# TPS54622_Schematic.net
KiCad netlist of a schematic drawn in Altium Designer
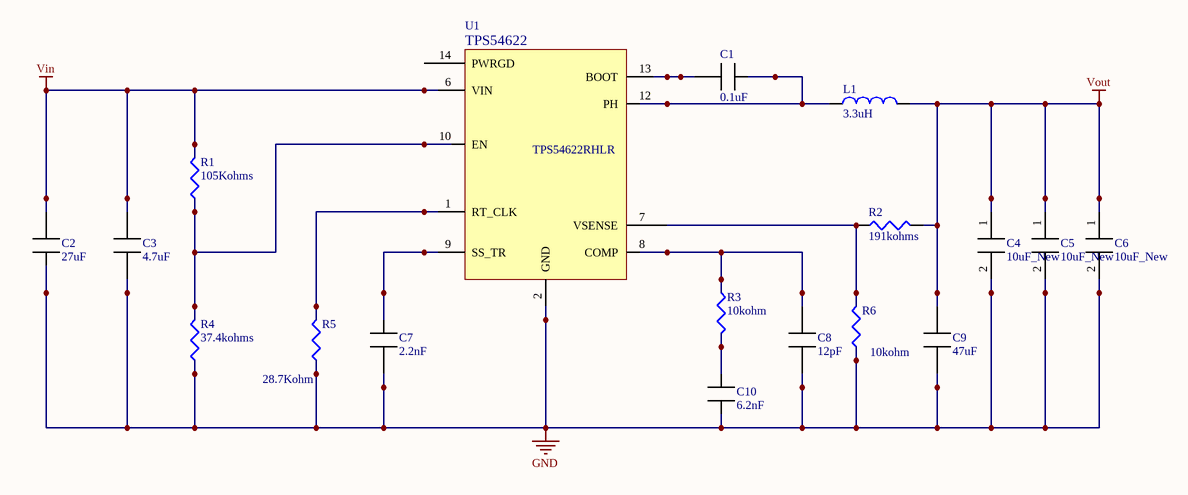
[diagram p0: TPS54622_Schematic.SchDoc]

(export (version "E")
  (design (tool "Eeschema 10.0.6"))
  (components
    (comp (ref "C1")
      (value "0.1uF")
      (footprint "C/R0805")
      (description "KEMET         C0805C104Z5VACTU.             CERAMIC CAPACITOR, 0.1UF, 50V, Y5V, +80,-20%, 0805")
      (fields
        (field (name "MANUFACTURER") "KEMET")
        (field (name "MANUFACTURER PART NUMBER") "C0805C104Z5VACTU")
      )
      (libsource (lib "TPS54622_Schematic_Library") (part "C0805C104Z5VACTU"))
    )
    (comp (ref "C2")
      (value "27uF")
      (footprint "CAPAE430X550N")
      (description "CAP ALUM POLY 27UF 20% 25V SMD")
      (fields
        (field (name "MANUFACTURER") "Panasonic")
        (field (name "MANUFACTURER PART NUMBER") "25SVPF27MX")
      )
      (libsource (lib "TPS54622_Schematic_Library") (part "25SVPF27MX"))
    )
    (comp (ref "C3")
      (value "4.7uF")
      (footprint "C/R0805")
      (description "CAP CER 4.7UF 10V Y5V 0805")
      (fields
        (field (name "MANUFACTURER") "Yageo")
        (field (name "MANUFACTURER PART NUMBER") "CC0805ZRY5V6BB475")
      )
      (libsource (lib "TPS54622_Schematic_Library") (part "CC0805ZRY5V6BB475"))
    )
    (comp (ref "C4")
      (value "10uF_New")
      (footprint "CAPPM7343X310N")
      (description "CAP TANT 10UF 35V 20% 2917")
      (fields
        (field (name "MANUFACTURER") "KEMET")
        (field (name "MANUFACTURER PART NUMBER") "T495D106M035ATE125")
      )
      (libsource (lib "TPS54622_Schematic_Library") (part "T495D106M035ATE125"))
    )
    (comp (ref "C5")
      (value "10uF_New")
      (footprint "CAPPM7343X310N")
      (description "CAP TANT 10UF 35V 20% 2917")
      (fields
        (field (name "MANUFACTURER") "KEMET")
        (field (name "MANUFACTURER PART NUMBER") "T495D106M035ATE125")
      )
      (libsource (lib "TPS54622_Schematic_Library") (part "T495D106M035ATE125"))
    )
    (comp (ref "C6")
      (value "10uF_New")
      (footprint "CAPPM7343X310N")
      (description "CAP TANT 10UF 35V 20% 2917")
      (fields
        (field (name "MANUFACTURER") "KEMET")
        (field (name "MANUFACTURER PART NUMBER") "T495D106M035ATE125")
      )
      (libsource (lib "TPS54622_Schematic_Library") (part "T495D106M035ATE125"))
    )
    (comp (ref "C7")
      (value "2.2nF")
      (footprint "C/R0805")
      (description "Cap Ceramic 0.0022uF 50V X7R 10% Pad SMD 0805 125C Bulk")
      (fields
        (field (name "MANUFACTURER") "KEMET")
        (field (name "MANUFACTURER PART NUMBER") "C0805C222K5RAC")
      )
      (libsource (lib "TPS54622_Schematic_Library") (part "C0805C222K5RAC"))
    )
    (comp (ref "C8")
      (value "12pF")
      (footprint "C/R0805")
      (description "CAP CER 12PF 50V C0G/NPO 0805")
      (fields
        (field (name "MANUFACTURER") "Yageo")
        (field (name "MANUFACTURER PART NUMBER") "CC0805JRNPO9BN120")
      )
      (libsource (lib "TPS54622_Schematic_Library") (part "CC0805JRNPO9BN120"))
    )
    (comp (ref "C9")
      (value "47uF")
      (footprint "C/R0805")
      (description "47µF 6.3V Ceramic Capacitor X5R 0805 (2012 Metric) 0.079\" L x 0.049\" W (2.00mm x 1.25mm)")
      (fields
        (field (name "MANUFACTURER") "Murata")
        (field (name "MANUFACTURER PART NUMBER") "GRM21BR60J476ME15K")
      )
      (libsource (lib "TPS54622_Schematic_Library") (part "GRM21BR60J476ME15K"))
    )
    (comp (ref "C10")
      (value "6.2nF")
      (footprint "C/R0805")
      (description "CAP CER 6200PF 50V C0G/NP0 0805")
      (fields
        (field (name "MANUFACTURER") "Murata")
        (field (name "MANUFACTURER PART NUMBER") "GRM2195C1H622JA01D")
      )
      (libsource (lib "TPS54622_Schematic_Library") (part "GRM2195C1H622JA01D"))
    )
    (comp (ref "L1")
      (value "3.3uH")
      (footprint "C/R0805")
      (fields
        (field (name "MANUFACTURER") "Taiyo Yuden")
        (field (name "MANUFACTURER PART NUMBER") "BRC2012T3R3MD")
        (field (name "TOLERANCE") "±20%")
      )
      (libsource (lib "TPS54622_Schematic_Library") (part "BRC2012T3R3MD"))
    )
    (comp (ref "R1")
      (value "105Kohms")
      (footprint "C/R0805")
      (description "RESISTOR, 0805, 105K, 0.1%, 0.125W")
      (fields
        (field (name "MANUFACTURER") "Panasonic")
        (field (name "MANUFACTURER PART NUMBER") "ERA-6AEB1053V")
      )
      (libsource (lib "TPS54622_Schematic_Library") (part "ERA-6AEB1053V"))
    )
    (comp (ref "R2")
      (value "191kohms")
      (footprint "C/R0805")
      (description "Res Thin Film 0805 191K Ohm 0.1% 1/8W 25ppm/C Molded SMD Punched Carrier T/R")
      (fields
        (field (name "MANUFACTURER") "Panasonic")
        (field (name "MANUFACTURER PART NUMBER") "ERA-6AEB1913V")
      )
      (libsource (lib "TPS54622_Schematic_Library") (part "ERA-6AEB1913V"))
    )
    (comp (ref "R3")
      (value "10kohm")
      (footprint "C/R0805")
      (description "RES SMD 10K OHM 1/4W 0805 WIDE")
      (fields (field (name "MANUFACTURER") "Rohm") (field (name "MANUFACTURER PART NUMBER") "LTR10EZPJ103"))
      (libsource (lib "TPS54622_Schematic_Library") (part "LTR10EZPJ103"))
    )
    (comp (ref "R4")
      (value "37.4kohms")
      (footprint "C/R0805")
      (description "Metal film resistor 37.4 kΩ SMD 0805 0.125 W")
      (fields
        (field (name "MANUFACTURER") "Panasonic")
        (field (name "MANUFACTURER PART NUMBER") "ERA6AEB3742V")
      )
      (libsource (lib "TPS54622_Schematic_Library") (part "ERA6AEB3742V"))
    )
    (comp (ref "R5")
      (value "28.7Kohm")
      (footprint "C/R0805")
      (description "RES SMD 28.7K OHM 0.1% 1/8W 0805")
      (fields
        (field (name "MANUFACTURER") "Susumu")
        (field (name "MANUFACTURER PART NUMBER") "RG2012P-2872-B-T5")
      )
      (libsource (lib "TPS54622_Schematic_Library") (part "RG2012P-2872-B-T5"))
    )
    (comp (ref "R6")
      (value "10kohm")
      (footprint "C/R0805")
      (description "RES SMD 10K OHM 1/4W 0805 WIDE")
      (fields (field (name "MANUFACTURER") "Rohm") (field (name "MANUFACTURER PART NUMBER") "LTR10EZPJ103"))
      (libsource (lib "TPS54622_Schematic_Library") (part "LTR10EZPJ103"))
    )
    (comp (ref "U1")
      (value "TPS54622RHLR")
      (footprint "QFN50P350X350X100-15N")
      (description "IC REG BUCK ADJ 6A SYNC 14QFN")
      (fields (field (name "MANUFACTURER") "Texas Instruments"))
      (libsource (lib "TPS54622_Schematic_Library") (part "TPS54622RHLR"))
    )
  )
  (nets
    (net (code "1") (name "GND") (class "Default")
      (node (ref "C10") (pin "1") (pinfunction "1_1") (pintype "passive"))
      (node (ref "C2") (pin "1") (pinfunction "1_1") (pintype "passive"))
      (node (ref "C3") (pin "1") (pinfunction "1_1") (pintype "passive"))
      (node (ref "C4") (pin "2") (pinfunction "2_2") (pintype "passive"))
      (node (ref "C5") (pin "2") (pinfunction "2_2") (pintype "passive"))
      (node (ref "C6") (pin "2") (pinfunction "2_2") (pintype "passive"))
      (node (ref "C7") (pin "1") (pinfunction "1_1") (pintype "passive"))
      (node (ref "C8") (pin "2") (pinfunction "2_2") (pintype "passive"))
      (node (ref "C9") (pin "1") (pinfunction "1_1") (pintype "passive"))
      (node (ref "R4") (pin "1") (pinfunction "1_1") (pintype "passive"))
      (node (ref "R5") (pin "1") (pinfunction "1_1") (pintype "passive"))
      (node (ref "R6") (pin "1") (pinfunction "1_1") (pintype "passive"))
      (node (ref "U1") (pin "2") (pinfunction "GND_2") (pintype "passive"))
    )
    (net (code "2") (name "Net-(C10-Pad2)") (class "Default")
      (node (ref "C10") (pin "2") (pinfunction "2_2") (pintype "passive"))
      (node (ref "R3") (pin "2") (pinfunction "2_2") (pintype "passive"))
    )
    (net (code "3") (name "Net-(U1-BOOT)") (class "Default")
      (node (ref "C1") (pin "1") (pinfunction "1_1") (pintype "passive"))
      (node (ref "U1") (pin "13") (pinfunction "BOOT_13") (pintype "passive"))
    )
    (net (code "4") (name "Net-(U1-COMP)") (class "Default")
      (node (ref "C8") (pin "1") (pinfunction "1_1") (pintype "passive"))
      (node (ref "R3") (pin "1") (pinfunction "1_1") (pintype "passive"))
      (node (ref "U1") (pin "8") (pinfunction "COMP_8") (pintype "passive"))
    )
    (net (code "5") (name "Net-(U1-EN)") (class "Default")
      (node (ref "R1") (pin "1") (pinfunction "1_1") (pintype "passive"))
      (node (ref "R4") (pin "2") (pinfunction "2_2") (pintype "passive"))
      (node (ref "U1") (pin "10") (pinfunction "EN_10") (pintype "passive"))
    )
    (net (code "6") (name "Net-(U1-PH)") (class "Default")
      (node (ref "C1") (pin "2") (pinfunction "2_2") (pintype "passive"))
      (node (ref "L1") (pin "1") (pinfunction "1_1") (pintype "passive"))
      (node (ref "U1") (pin "12") (pinfunction "PH_12") (pintype "passive"))
    )
    (net (code "7") (name "Net-(U1-RT_CLK)") (class "Default")
      (node (ref "R5") (pin "2") (pinfunction "2_2") (pintype "passive"))
      (node (ref "U1") (pin "1") (pinfunction "RT_CLK_1") (pintype "passive"))
    )
    (net (code "8") (name "Net-(U1-SS_TR)") (class "Default")
      (node (ref "C7") (pin "2") (pinfunction "2_2") (pintype "passive"))
      (node (ref "U1") (pin "9") (pinfunction "SS_TR_9") (pintype "passive"))
    )
    (net (code "9") (name "Net-(U1-VSENSE)") (class "Default")
      (node (ref "R2") (pin "1") (pinfunction "1_1") (pintype "passive"))
      (node (ref "R6") (pin "2") (pinfunction "2_2") (pintype "passive"))
      (node (ref "U1") (pin "7") (pinfunction "VSENSE_7") (pintype "passive"))
    )
    (net (code "10") (name "Vin") (class "Default")
      (node (ref "C2") (pin "2") (pinfunction "2_2") (pintype "passive"))
      (node (ref "C3") (pin "2") (pinfunction "2_2") (pintype "passive"))
      (node (ref "R1") (pin "2") (pinfunction "2_2") (pintype "passive"))
      (node (ref "U1") (pin "6") (pinfunction "VIN_6") (pintype "passive"))
    )
    (net (code "11") (name "Vout") (class "Default")
      (node (ref "C4") (pin "1") (pinfunction "1_1") (pintype "passive"))
      (node (ref "C5") (pin "1") (pinfunction "1_1") (pintype "passive"))
      (node (ref "C6") (pin "1") (pinfunction "1_1") (pintype "passive"))
      (node (ref "C9") (pin "2") (pinfunction "2_2") (pintype "passive"))
      (node (ref "L1") (pin "2") (pinfunction "2_2") (pintype "passive"))
      (node (ref "R2") (pin "2") (pinfunction "2_2") (pintype "passive"))
    )
    (net (code "12") (name "unconnected-(U1-PWRGD-Pad14)") (class "Default")
      (node (ref "U1") (pin "14") (pinfunction "PWRGD_14") (pintype "passive"))
    )
  )
)
